# encoder_step2.net
KiCad netlist of a schematic drawn in EAGLE
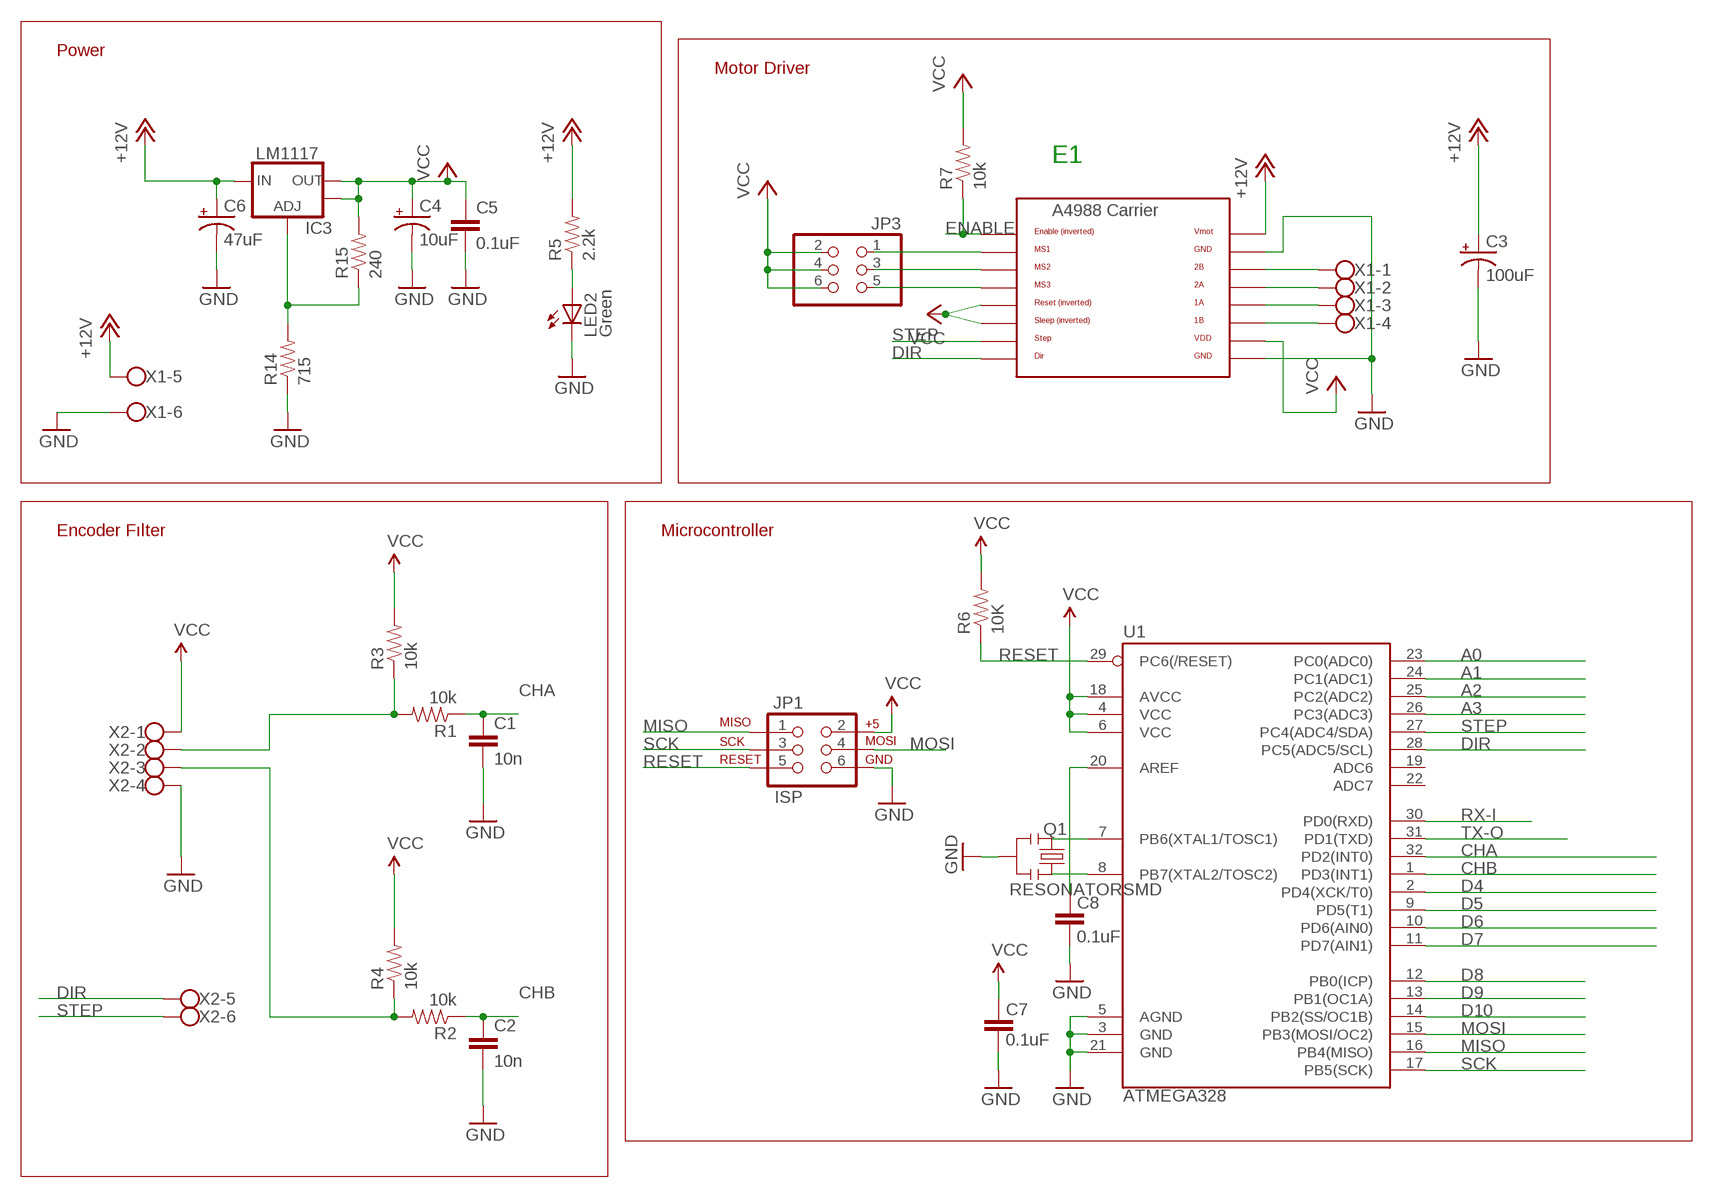
[diagram p0: schematic, sheet 1]

(export (version "E")
  (design (tool "Eeschema 10.0.6"))
  (components
    (comp (ref "C1")
      (value "10n")
      (footprint "eagle-import:0805")
      (libsource (lib "eagle-import") (part "2.2UF-25V-+80/-20(0805)"))
    )
    (comp (ref "C2")
      (value "10n")
      (footprint "eagle-import:0805")
      (libsource (lib "eagle-import") (part "2.2UF-25V-+80/-20(0805)"))
    )
    (comp (ref "C3")
      (value "100uF")
      (footprint "eagle-import:153CLV-0605")
      (libsource (lib "eagle-import") (part "CPOL-US153CLV-0605"))
    )
    (comp (ref "C4")
      (value "10uF")
      (footprint "eagle-import:EIA3216")
      (libsource (lib "eagle-import") (part "CAP_POL1206"))
    )
    (comp (ref "C5")
      (value "0.1uF")
      (footprint "eagle-import:0805")
      (libsource (lib "eagle-import") (part "CAP0805"))
    )
    (comp (ref "C6")
      (value "47uF")
      (footprint "eagle-import:PANASONIC_D")
      (libsource (lib "eagle-import") (part "CAP_POLD"))
    )
    (comp (ref "C7")
      (value "0.1uF")
      (footprint "eagle-import:0805")
      (libsource (lib "eagle-import") (part "CAP0805"))
    )
    (comp (ref "C8")
      (value "0.1uF")
      (footprint "eagle-import:0805")
      (libsource (lib "eagle-import") (part "CAP0805"))
    )
    (comp (ref "IC3")
      (value "LM1117")
      (footprint "eagle-import:SOT223-ALT1")
      (libsource (lib "eagle-import") (part "V_REG_LM1117ALT1"))
    )
    (comp (ref "JP1")
      (value "ISP")
      (footprint "eagle-import:2X3")
      (libsource (lib "eagle-import") (part "AVR_SPI_PRG_6PTH"))
    )
    (comp (ref "JP3")
      (value "PINHD-2X3")
      (footprint "eagle-import:2X03")
      (libsource (lib "eagle-import") (part "PINHD-2X3"))
    )
    (comp (ref "LED2")
      (value "Green")
      (footprint "eagle-import:LED-1206-NO_SILK")
      (libsource (lib "eagle-import") (part "LED1206-NS"))
    )
    (comp (ref "Q1")
      (value "RESONATORSMD")
      (footprint "eagle-import:RESONATOR-SMD")
      (libsource (lib "eagle-import") (part "RESONATORSMD"))
    )
    (comp (ref "R1")
      (value "10k")
      (footprint "eagle-import:0805")
      (libsource (lib "eagle-import") (part "SparkFun-Passives_RESISTOR0805-RES"))
    )
    (comp (ref "R2")
      (value "10k")
      (footprint "eagle-import:0805")
      (libsource (lib "eagle-import") (part "SparkFun-Passives_RESISTOR0805-RES"))
    )
    (comp (ref "R3")
      (value "10k")
      (footprint "eagle-import:0805")
      (libsource (lib "eagle-import") (part "SparkFun-Passives_RESISTOR0805-RES"))
    )
    (comp (ref "R4")
      (value "10k")
      (footprint "eagle-import:0805")
      (libsource (lib "eagle-import") (part "SparkFun-Passives_RESISTOR0805-RES"))
    )
    (comp (ref "R5")
      (value "2.2k")
      (footprint "eagle-import:0805")
      (libsource (lib "eagle-import") (part "RESISTOR0805-RES"))
    )
    (comp (ref "R6")
      (value "10K")
      (footprint "eagle-import:0805")
      (libsource (lib "eagle-import") (part "RESISTOR0805-RES"))
    )
    (comp (ref "R7")
      (value "10k")
      (footprint "eagle-import:0805")
      (libsource (lib "eagle-import") (part "SparkFun-Passives_RESISTOR0805-RES"))
    )
    (comp (ref "R14")
      (value "715")
      (footprint "eagle-import:0805")
      (libsource (lib "eagle-import") (part "RESISTOR0805-RES"))
    )
    (comp (ref "R15")
      (value "240")
      (footprint "eagle-import:0805")
      (libsource (lib "eagle-import") (part "RESISTOR0805-RES"))
    )
    (comp (ref "U$5")
      (value "A4988BREAKOUT")
      (footprint "eagle-import:A4988BREAKOUT")
      (libsource (lib "eagle-import") (part "A4988BREAKOUT"))
    )
    (comp (ref "U1")
      (value "ATMEGA328")
      (footprint "eagle-import:TQFP32-08")
      (libsource (lib "eagle-import") (part "ATMEGA168"))
    )
    (comp (ref "X1")
      (value "W237-6")
      (footprint "eagle-import:W237-6")
      (libsource (lib "eagle-import") (part "W237-6"))
    )
    (comp (ref "X2")
      (value "W237-6")
      (footprint "eagle-import:W237-6")
      (libsource (lib "eagle-import") (part "W237-6"))
    )
  )
  (nets
    (net (code "1") (name "+12V") (class "Default")
      (node (ref "C3") (pin "+") (pinfunction "+_+") (pintype "passive"))
      (node (ref "C6") (pin "+") (pinfunction "+_+") (pintype "passive"))
      (node (ref "IC3") (pin "3") (pinfunction "IN_3") (pintype "input"))
      (node (ref "R5") (pin "2") (pinfunction "2_2") (pintype "passive"))
      (node (ref "U$5") (pin "VMOT") (pinfunction "VMOT_VMOT") (pintype "power_in"))
      (node (ref "X1") (pin "5") (pinfunction "KL_5") (pintype "passive"))
    )
    (net (code "2") (name "/A0") (class "Default")
      (node (ref "U1") (pin "23") (pinfunction "PC0(ADC0)_23") (pintype "bidirectional"))
    )
    (net (code "3") (name "/A1") (class "Default")
      (node (ref "U1") (pin "24") (pinfunction "PC1(ADC1)_24") (pintype "bidirectional"))
    )
    (net (code "4") (name "/A2") (class "Default")
      (node (ref "U1") (pin "25") (pinfunction "PC2(ADC2)_25") (pintype "bidirectional"))
    )
    (net (code "5") (name "/A3") (class "Default")
      (node (ref "U1") (pin "26") (pinfunction "PC3(ADC3)_26") (pintype "bidirectional"))
    )
    (net (code "6") (name "/CHA") (class "Default")
      (node (ref "C1") (pin "1") (pinfunction "1_1") (pintype "passive"))
      (node (ref "R1") (pin "1") (pinfunction "1_1") (pintype "passive"))
      (node (ref "U1") (pin "32") (pinfunction "PD2(INT0)_32") (pintype "bidirectional"))
    )
    (net (code "7") (name "/CHB") (class "Default")
      (node (ref "C2") (pin "1") (pinfunction "1_1") (pintype "passive"))
      (node (ref "R2") (pin "1") (pinfunction "1_1") (pintype "passive"))
      (node (ref "U1") (pin "1") (pinfunction "PD3(INT1)_1") (pintype "bidirectional"))
    )
    (net (code "8") (name "/D4") (class "Default")
      (node (ref "U1") (pin "2") (pinfunction "PD4(XCK/T0)_2") (pintype "bidirectional"))
    )
    (net (code "9") (name "/D5") (class "Default")
      (node (ref "U1") (pin "9") (pinfunction "PD5(T1)_9") (pintype "bidirectional"))
    )
    (net (code "10") (name "/D6") (class "Default")
      (node (ref "U1") (pin "10") (pinfunction "PD6(AIN0)_10") (pintype "bidirectional"))
    )
    (net (code "11") (name "/D7") (class "Default")
      (node (ref "U1") (pin "11") (pinfunction "PD7(AIN1)_11") (pintype "bidirectional"))
    )
    (net (code "12") (name "/D8") (class "Default")
      (node (ref "U1") (pin "12") (pinfunction "PB0(ICP)_12") (pintype "bidirectional"))
    )
    (net (code "13") (name "/D9") (class "Default")
      (node (ref "U1") (pin "13") (pinfunction "PB1(OC1A)_13") (pintype "bidirectional"))
    )
    (net (code "14") (name "/D10") (class "Default")
      (node (ref "U1") (pin "14") (pinfunction "PB2(SS/OC1B)_14") (pintype "bidirectional"))
    )
    (net (code "15") (name "/DIR") (class "Default")
      (node (ref "U$5") (pin "DIR") (pinfunction "DIR_DIR") (pintype "input"))
      (node (ref "U1") (pin "28") (pinfunction "PC5(ADC5/SCL)_28") (pintype "bidirectional"))
      (node (ref "X2") (pin "5") (pinfunction "KL_5") (pintype "passive"))
    )
    (net (code "16") (name "/ENABLE") (class "Default")
      (node (ref "R7") (pin "1") (pinfunction "1_1") (pintype "passive"))
      (node (ref "U$5") (pin "EN") (pinfunction "EN_EN") (pintype "input"))
    )
    (net (code "17") (name "/MISO") (class "Default")
      (node (ref "JP1") (pin "1") (pinfunction "1_1") (pintype "passive"))
      (node (ref "U1") (pin "16") (pinfunction "PB4(MISO)_16") (pintype "bidirectional"))
    )
    (net (code "18") (name "/MOSI") (class "Default")
      (node (ref "JP1") (pin "4") (pinfunction "4_4") (pintype "passive"))
      (node (ref "U1") (pin "15") (pinfunction "PB3(MOSI/OC2)_15") (pintype "bidirectional"))
    )
    (net (code "19") (name "/RESET") (class "Default")
      (node (ref "JP1") (pin "5") (pinfunction "5_5") (pintype "passive"))
      (node (ref "R6") (pin "1") (pinfunction "1_1") (pintype "passive"))
      (node (ref "U1") (pin "29") (pinfunction "PC6(/RESET)_29") (pintype "bidirectional"))
    )
    (net (code "20") (name "/RX-I") (class "Default")
      (node (ref "U1") (pin "30") (pinfunction "PD0(RXD)_30") (pintype "bidirectional"))
    )
    (net (code "21") (name "/SCK") (class "Default")
      (node (ref "JP1") (pin "3") (pinfunction "3_3") (pintype "passive"))
      (node (ref "U1") (pin "17") (pinfunction "PB5(SCK)_17") (pintype "bidirectional"))
    )
    (net (code "22") (name "/STEP") (class "Default")
      (node (ref "U$5") (pin "STEP") (pinfunction "STEP_STEP") (pintype "input"))
      (node (ref "U1") (pin "27") (pinfunction "PC4(ADC4/SDA)_27") (pintype "bidirectional"))
      (node (ref "X2") (pin "6") (pinfunction "KL_6") (pintype "passive"))
    )
    (net (code "23") (name "/TX-O") (class "Default")
      (node (ref "U1") (pin "31") (pinfunction "PD1(TXD)_31") (pintype "bidirectional"))
    )
    (net (code "24") (name "GND") (class "Default")
      (node (ref "C1") (pin "2") (pinfunction "2_2") (pintype "passive"))
      (node (ref "C2") (pin "2") (pinfunction "2_2") (pintype "passive"))
      (node (ref "C3") (pin "-") (pinfunction "-_-") (pintype "passive"))
      (node (ref "C4") (pin "C") (pinfunction "-_C") (pintype "passive"))
      (node (ref "C5") (pin "2") (pinfunction "2_2") (pintype "passive"))
      (node (ref "C6") (pin "-") (pinfunction "-_-") (pintype "passive"))
      (node (ref "C7") (pin "1") (pinfunction "1_1") (pintype "passive"))
      (node (ref "C8") (pin "1") (pinfunction "1_1") (pintype "passive"))
      (node (ref "JP1") (pin "6") (pinfunction "6_6") (pintype "passive"))
      (node (ref "LED2") (pin "C") (pinfunction "C_C") (pintype "passive"))
      (node (ref "Q1") (pin "2") (pinfunction "2_2") (pintype "passive"))
      (node (ref "R14") (pin "1") (pinfunction "1_1") (pintype "passive"))
      (node (ref "U$5") (pin "GND") (pinfunction "GND_GND") (pintype "power_in"))
      (node (ref "U$5") (pin "GND@0") (pinfunction "GND_GND@0") (pintype "power_in"))
      (node (ref "U1") (pin "21") (pinfunction "GND_21") (pintype "bidirectional"))
      (node (ref "U1") (pin "3") (pinfunction "GND_3") (pintype "bidirectional"))
      (node (ref "U1") (pin "5") (pinfunction "AGND_5") (pintype "bidirectional"))
      (node (ref "X1") (pin "6") (pinfunction "KL_6") (pintype "passive"))
      (node (ref "X2") (pin "4") (pinfunction "KL_4") (pintype "passive"))
    )
    (net (code "25") (name "Net-(IC3-ADJ)") (class "Default")
      (node (ref "IC3") (pin "1") (pinfunction "ADJ_1") (pintype "input"))
      (node (ref "R14") (pin "2") (pinfunction "2_2") (pintype "passive"))
      (node (ref "R15") (pin "1") (pinfunction "1_1") (pintype "passive"))
    )
    (net (code "26") (name "Net-(JP3-Pad1)") (class "Default")
      (node (ref "JP3") (pin "1") (pinfunction "1_1") (pintype "passive"))
      (node (ref "U$5") (pin "MS1") (pinfunction "MS1_MS1") (pintype "input"))
    )
    (net (code "27") (name "Net-(JP3-Pad3)") (class "Default")
      (node (ref "JP3") (pin "3") (pinfunction "3_3") (pintype "passive"))
      (node (ref "U$5") (pin "MS2") (pinfunction "MS2_MS2") (pintype "input"))
    )
    (net (code "28") (name "Net-(JP3-Pad5)") (class "Default")
      (node (ref "JP3") (pin "5") (pinfunction "5_5") (pintype "passive"))
      (node (ref "U$5") (pin "MS3") (pinfunction "MS3_MS3") (pintype "input"))
    )
    (net (code "29") (name "Net-(LED2-PadA)") (class "Default")
      (node (ref "LED2") (pin "A") (pinfunction "A_A") (pintype "passive"))
      (node (ref "R5") (pin "1") (pinfunction "1_1") (pintype "passive"))
    )
    (net (code "30") (name "Net-(U1-AREF)") (class "Default")
      (node (ref "C8") (pin "2") (pinfunction "2_2") (pintype "passive"))
      (node (ref "U1") (pin "20") (pinfunction "AREF_20") (pintype "bidirectional"))
    )
    (net (code "31") (name "Net-(U1-PB6(XTAL1{slash}TOSC1))") (class "Default")
      (node (ref "Q1") (pin "3") (pinfunction "3_3") (pintype "passive"))
      (node (ref "U1") (pin "7") (pinfunction "PB6(XTAL1/TOSC1)_7") (pintype "bidirectional"))
    )
    (net (code "32") (name "Net-(U1-PB7(XTAL2{slash}TOSC2))") (class "Default")
      (node (ref "Q1") (pin "1") (pinfunction "1_1") (pintype "passive"))
      (node (ref "U1") (pin "8") (pinfunction "PB7(XTAL2/TOSC2)_8") (pintype "bidirectional"))
    )
    (net (code "33") (name "Net-(X1A-KL)") (class "Default")
      (node (ref "U$5") (pin "2B") (pinfunction "2B_2B") (pintype "output"))
      (node (ref "X1") (pin "1") (pinfunction "KL_1") (pintype "passive"))
    )
    (net (code "34") (name "Net-(X1B-KL)") (class "Default")
      (node (ref "U$5") (pin "2A") (pinfunction "2A_2A") (pintype "output"))
      (node (ref "X1") (pin "2") (pinfunction "KL_2") (pintype "passive"))
    )
    (net (code "35") (name "Net-(X1C-KL)") (class "Default")
      (node (ref "U$5") (pin "1A") (pinfunction "1A_1A") (pintype "output"))
      (node (ref "X1") (pin "3") (pinfunction "KL_3") (pintype "passive"))
    )
    (net (code "36") (name "Net-(X1D-KL)") (class "Default")
      (node (ref "U$5") (pin "1B") (pinfunction "1B_1B") (pintype "output"))
      (node (ref "X1") (pin "4") (pinfunction "KL_4") (pintype "passive"))
    )
    (net (code "37") (name "Net-(X2B-KL)") (class "Default")
      (node (ref "R1") (pin "2") (pinfunction "2_2") (pintype "passive"))
      (node (ref "R3") (pin "1") (pinfunction "1_1") (pintype "passive"))
      (node (ref "X2") (pin "2") (pinfunction "KL_2") (pintype "passive"))
    )
    (net (code "38") (name "Net-(X2C-KL)") (class "Default")
      (node (ref "R2") (pin "2") (pinfunction "2_2") (pintype "passive"))
      (node (ref "R4") (pin "1") (pinfunction "1_1") (pintype "passive"))
      (node (ref "X2") (pin "3") (pinfunction "KL_3") (pintype "passive"))
    )
    (net (code "39") (name "VCC") (class "Default")
      (node (ref "C4") (pin "A") (pinfunction "+_A") (pintype "passive"))
      (node (ref "C5") (pin "1") (pinfunction "1_1") (pintype "passive"))
      (node (ref "C7") (pin "2") (pinfunction "2_2") (pintype "passive"))
      (node (ref "IC3") (pin "2") (pinfunction "OUT_2") (pintype "output"))
      (node (ref "IC3") (pin "4") (pinfunction "OUT_4") (pintype "output"))
      (node (ref "JP1") (pin "2") (pinfunction "2_2") (pintype "passive"))
      (node (ref "JP3") (pin "2") (pinfunction "2_2") (pintype "passive"))
      (node (ref "JP3") (pin "4") (pinfunction "4_4") (pintype "passive"))
      (node (ref "JP3") (pin "6") (pinfunction "6_6") (pintype "passive"))
      (node (ref "R15") (pin "2") (pinfunction "2_2") (pintype "passive"))
      (node (ref "R3") (pin "2") (pinfunction "2_2") (pintype "passive"))
      (node (ref "R4") (pin "2") (pinfunction "2_2") (pintype "passive"))
      (node (ref "R6") (pin "2") (pinfunction "2_2") (pintype "passive"))
      (node (ref "R7") (pin "2") (pinfunction "2_2") (pintype "passive"))
      (node (ref "U$5") (pin "RST") (pinfunction "RST_RST") (pintype "input"))
      (node (ref "U$5") (pin "SLP") (pinfunction "SLEEP_SLP") (pintype "input"))
      (node (ref "U$5") (pin "VDD") (pinfunction "VDD_VDD") (pintype "power_in"))
      (node (ref "U1") (pin "18") (pinfunction "AVCC_18") (pintype "bidirectional"))
      (node (ref "U1") (pin "4") (pinfunction "VCC_4") (pintype "bidirectional"))
      (node (ref "U1") (pin "6") (pinfunction "VCC_6") (pintype "bidirectional"))
      (node (ref "X2") (pin "1") (pinfunction "KL_1") (pintype "passive"))
    )
    (net (code "40") (name "unconnected-(U1-ADC6-Pad19)") (class "Default")
      (node (ref "U1") (pin "19") (pinfunction "ADC6_19") (pintype "bidirectional"))
    )
    (net (code "41") (name "unconnected-(U1-ADC7-Pad22)") (class "Default")
      (node (ref "U1") (pin "22") (pinfunction "ADC7_22") (pintype "bidirectional"))
    )
  )
)
